# Sheet4.net
KiCad netlist of a schematic drawn in Altium Designer
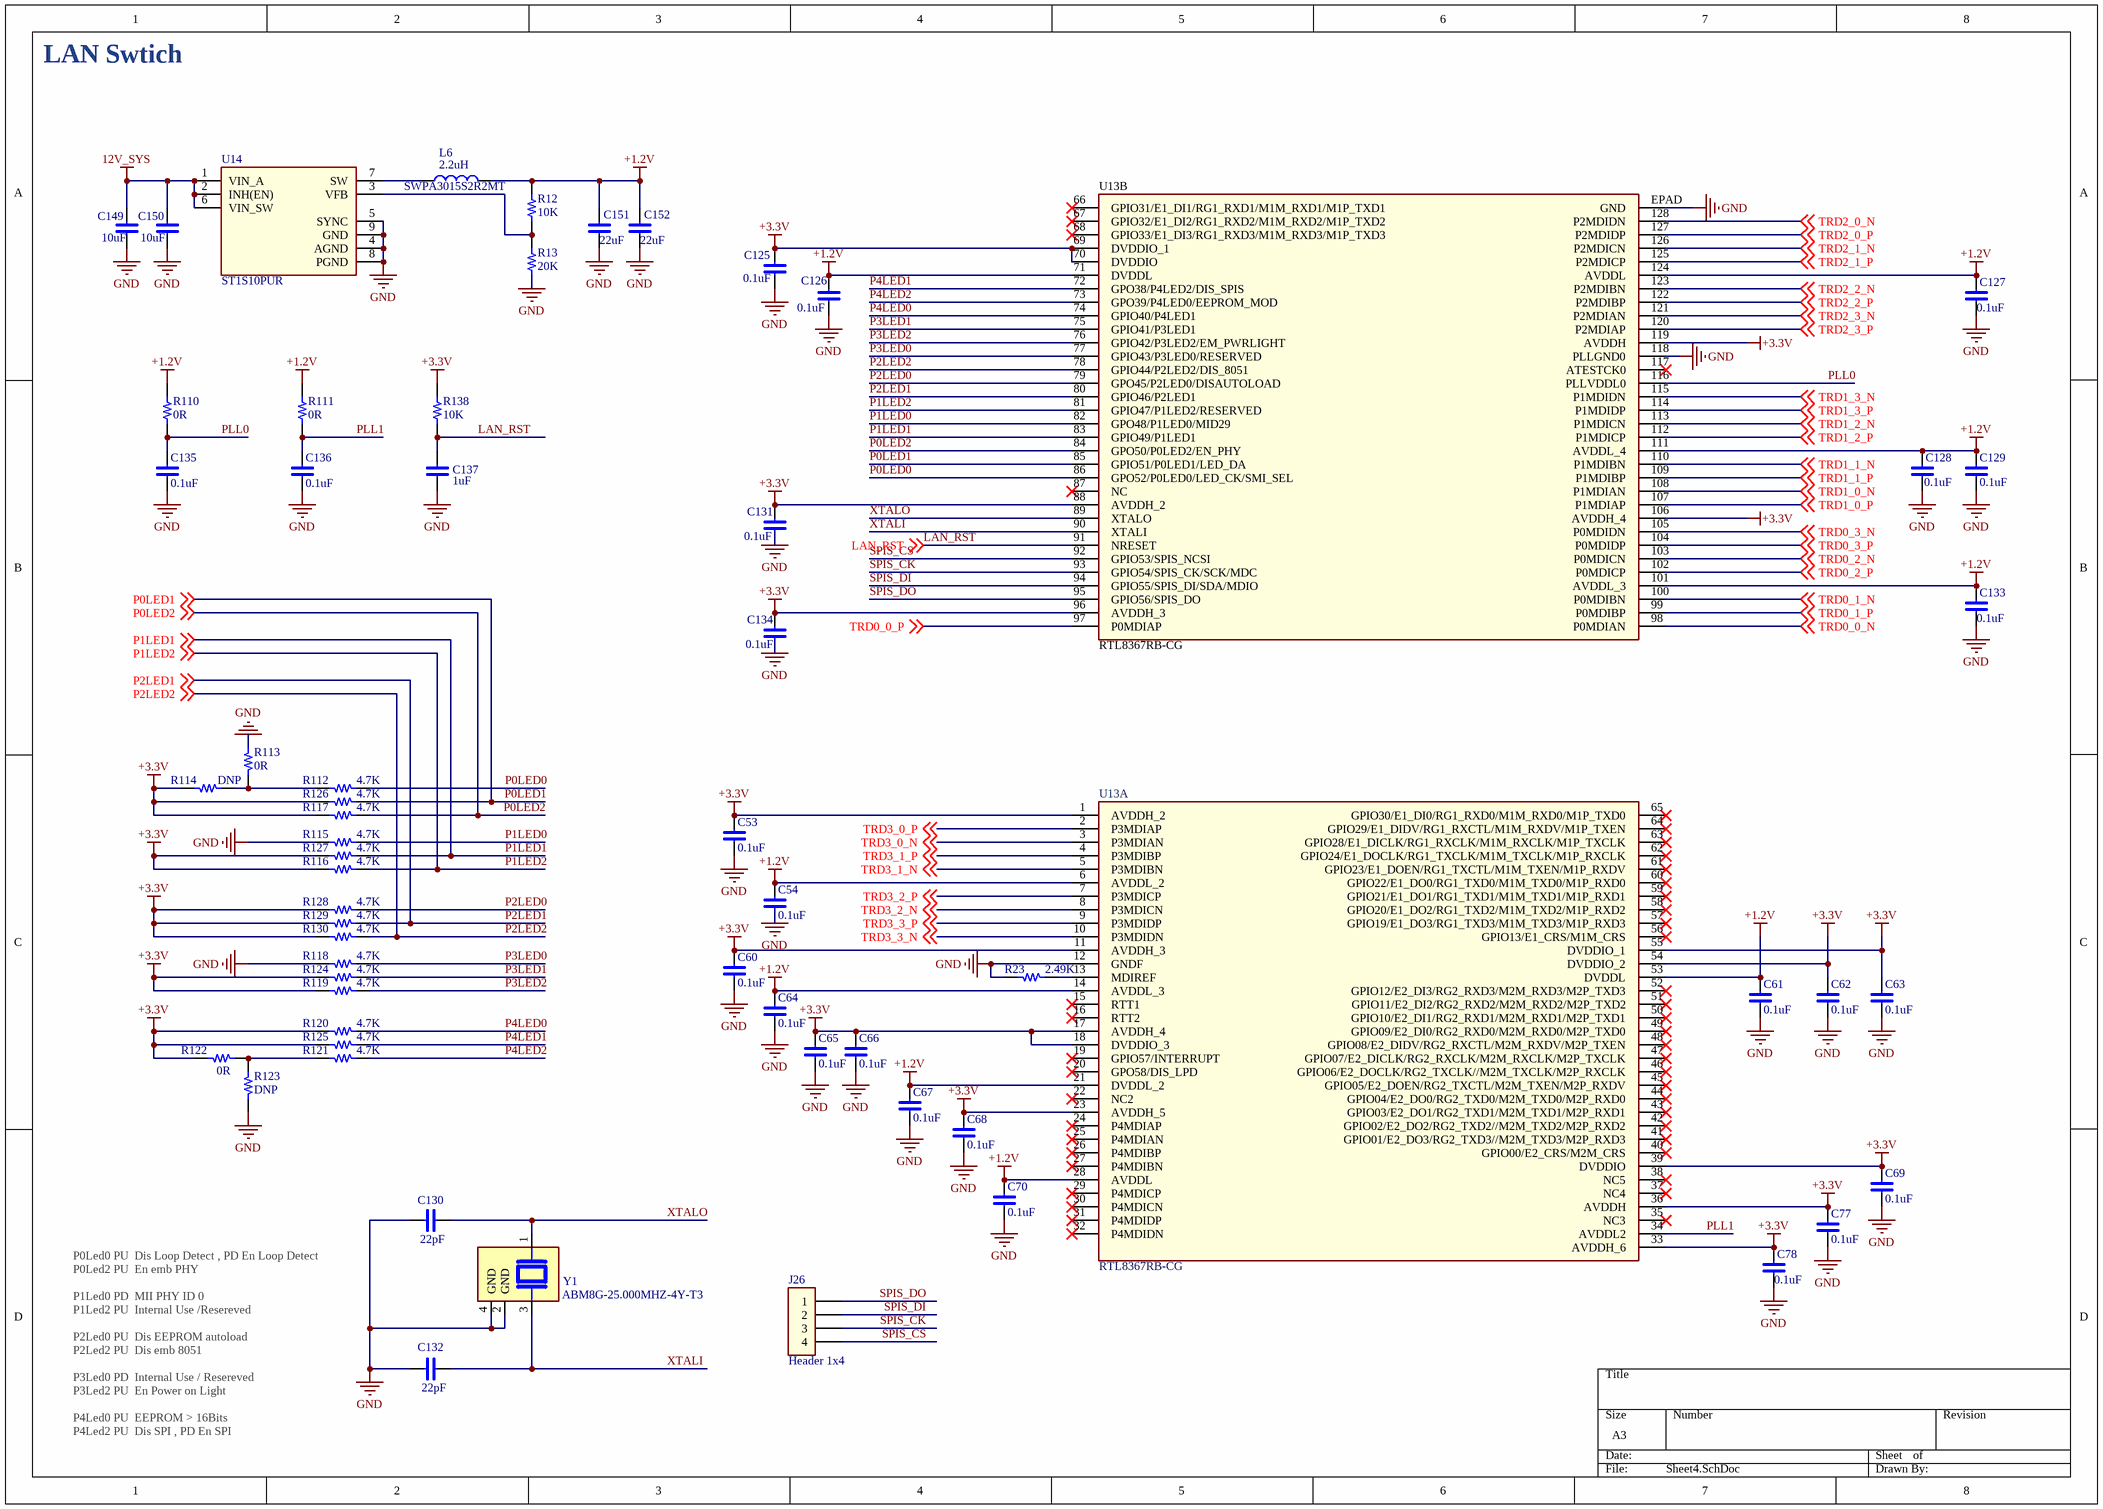
[diagram p0: Sheet4.SchDoc]

(export (version "E")
  (design (tool "Eeschema 10.0.6"))
  (components
    (comp (ref "C53")
      (value "0.1uF")
      (footprint "C-0402/1005")
      (description "CAP CER 0.1UF 16V X7R 0402")
      (fields (field (name "MFR. PART NO.") "GCM155R71C104KA55D"))
      (libsource (lib "Custom_Library") (part "Capacitor-NonPolar"))
    )
    (comp (ref "C54")
      (value "0.1uF")
      (footprint "C-0402/1005")
      (description "CAP CER 0.1UF 16V X7R 0402")
      (fields (field (name "MFR. PART NO.") "GCM155R71C104KA55D"))
      (libsource (lib "Custom_Library") (part "Capacitor-NonPolar"))
    )
    (comp (ref "C60")
      (value "0.1uF")
      (footprint "C-0402/1005")
      (description "CAP CER 0.1UF 16V X7R 0402")
      (fields (field (name "MFR. PART NO.") "GCM155R71C104KA55D"))
      (libsource (lib "Custom_Library") (part "Capacitor-NonPolar"))
    )
    (comp (ref "C61")
      (value "0.1uF")
      (footprint "C-0402/1005")
      (description "CAP CER 0.1UF 16V X7R 0402")
      (fields (field (name "MFR. PART NO.") "GCM155R71C104KA55D"))
      (libsource (lib "Custom_Library") (part "Capacitor-NonPolar"))
    )
    (comp (ref "C62")
      (value "0.1uF")
      (footprint "C-0402/1005")
      (description "CAP CER 0.1UF 16V X7R 0402")
      (fields (field (name "MFR. PART NO.") "GCM155R71C104KA55D"))
      (libsource (lib "Custom_Library") (part "Capacitor-NonPolar"))
    )
    (comp (ref "C63")
      (value "0.1uF")
      (footprint "C-0402/1005")
      (description "CAP CER 0.1UF 16V X7R 0402")
      (fields (field (name "MFR. PART NO.") "GCM155R71C104KA55D"))
      (libsource (lib "Custom_Library") (part "Capacitor-NonPolar"))
    )
    (comp (ref "C64")
      (value "0.1uF")
      (footprint "C-0402/1005")
      (description "CAP CER 0.1UF 16V X7R 0402")
      (fields (field (name "MFR. PART NO.") "GCM155R71C104KA55D"))
      (libsource (lib "Custom_Library") (part "Capacitor-NonPolar"))
    )
    (comp (ref "C65")
      (value "0.1uF")
      (footprint "C-0402/1005")
      (description "CAP CER 0.1UF 16V X7R 0402")
      (fields (field (name "MFR. PART NO.") "GCM155R71C104KA55D"))
      (libsource (lib "Custom_Library") (part "Capacitor-NonPolar"))
    )
    (comp (ref "C66")
      (value "0.1uF")
      (footprint "C-0402/1005")
      (description "CAP CER 0.1UF 16V X7R 0402")
      (fields (field (name "MFR. PART NO.") "GCM155R71C104KA55D"))
      (libsource (lib "Custom_Library") (part "Capacitor-NonPolar"))
    )
    (comp (ref "C67")
      (value "0.1uF")
      (footprint "C-0402/1005")
      (description "CAP CER 0.1UF 16V X7R 0402")
      (fields (field (name "MFR. PART NO.") "GCM155R71C104KA55D"))
      (libsource (lib "Custom_Library") (part "Capacitor-NonPolar"))
    )
    (comp (ref "C68")
      (value "0.1uF")
      (footprint "C-0402/1005")
      (description "CAP CER 0.1UF 16V X7R 0402")
      (fields (field (name "MFR. PART NO.") "GCM155R71C104KA55D"))
      (libsource (lib "Custom_Library") (part "Capacitor-NonPolar"))
    )
    (comp (ref "C69")
      (value "0.1uF")
      (footprint "C-0402/1005")
      (description "CAP CER 0.1UF 16V X7R 0402")
      (fields (field (name "MFR. PART NO.") "GCM155R71C104KA55D"))
      (libsource (lib "Custom_Library") (part "Capacitor-NonPolar"))
    )
    (comp (ref "C70")
      (value "0.1uF")
      (footprint "C-0402/1005")
      (description "CAP CER 0.1UF 16V X7R 0402")
      (fields (field (name "MFR. PART NO.") "GCM155R71C104KA55D"))
      (libsource (lib "Custom_Library") (part "Capacitor-NonPolar"))
    )
    (comp (ref "C77")
      (value "0.1uF")
      (footprint "C-0402/1005")
      (description "CAP CER 0.1UF 16V X7R 0402")
      (fields (field (name "MFR. PART NO.") "GCM155R71C104KA55D"))
      (libsource (lib "Custom_Library") (part "Capacitor-NonPolar"))
    )
    (comp (ref "C78")
      (value "0.1uF")
      (footprint "C-0402/1005")
      (description "CAP CER 0.1UF 16V X7R 0402")
      (fields (field (name "MFR. PART NO.") "GCM155R71C104KA55D"))
      (libsource (lib "Custom_Library") (part "Capacitor-NonPolar"))
    )
    (comp (ref "C125")
      (value "0.1uF")
      (footprint "C-0402/1005")
      (description "CAP CER 0.1UF 16V X7R 0402")
      (fields (field (name "MFR. PART NO.") "GCM155R71C104KA55D"))
      (libsource (lib "Custom_Library") (part "Capacitor-NonPolar"))
    )
    (comp (ref "C126")
      (value "0.1uF")
      (footprint "C-0402/1005")
      (description "CAP CER 0.1UF 16V X7R 0402")
      (fields (field (name "MFR. PART NO.") "GCM155R71C104KA55D"))
      (libsource (lib "Custom_Library") (part "Capacitor-NonPolar"))
    )
    (comp (ref "C127")
      (value "0.1uF")
      (footprint "C-0402/1005")
      (description "CAP CER 0.1UF 16V X7R 0402")
      (fields (field (name "MFR. PART NO.") "GCM155R71C104KA55D"))
      (libsource (lib "Custom_Library") (part "Capacitor-NonPolar"))
    )
    (comp (ref "C128")
      (value "0.1uF")
      (footprint "C-0402/1005")
      (description "CAP CER 0.1UF 16V X7R 0402")
      (fields (field (name "MFR. PART NO.") "GCM155R71C104KA55D"))
      (libsource (lib "Custom_Library") (part "Capacitor-NonPolar"))
    )
    (comp (ref "C129")
      (value "0.1uF")
      (footprint "C-0402/1005")
      (description "CAP CER 0.1UF 16V X7R 0402")
      (fields (field (name "MFR. PART NO.") "GCM155R71C104KA55D"))
      (libsource (lib "Custom_Library") (part "Capacitor-NonPolar"))
    )
    (comp (ref "C130")
      (value "22pF")
      (footprint "C-0402/1005")
      (description "CAP CER 0.1UF 16V X7R 0402")
      (fields (field (name "MFR. PART NO.") "GCM155R71C104KA55D"))
      (libsource (lib "") (part "Capacitor-NonPolar_1"))
    )
    (comp (ref "C131")
      (value "0.1uF")
      (footprint "C-0402/1005")
      (description "CAP CER 0.1UF 16V X7R 0402")
      (fields (field (name "MFR. PART NO.") "GCM155R71C104KA55D"))
      (libsource (lib "Custom_Library") (part "Capacitor-NonPolar"))
    )
    (comp (ref "C132")
      (value "22pF")
      (footprint "C-0402/1005")
      (description "CAP CER 0.1UF 16V X7R 0402")
      (fields (field (name "MFR. PART NO.") "GCM155R71C104KA55D"))
      (libsource (lib "") (part "Capacitor-NonPolar_1"))
    )
    (comp (ref "C133")
      (value "0.1uF")
      (footprint "C-0402/1005")
      (description "CAP CER 0.1UF 16V X7R 0402")
      (fields (field (name "MFR. PART NO.") "GCM155R71C104KA55D"))
      (libsource (lib "Custom_Library") (part "Capacitor-NonPolar"))
    )
    (comp (ref "C134")
      (value "0.1uF")
      (footprint "C-0402/1005")
      (description "CAP CER 0.1UF 16V X7R 0402")
      (fields (field (name "MFR. PART NO.") "GCM155R71C104KA55D"))
      (libsource (lib "Custom_Library") (part "Capacitor-NonPolar"))
    )
    (comp (ref "C135")
      (value "0.1uF")
      (footprint "C-0402/1005")
      (description "CAP CER 0.1UF 16V X7R 0402")
      (fields (field (name "MFR. PART NO.") "GCM155R71C104KA55D"))
      (libsource (lib "Custom_Library") (part "Capacitor-NonPolar"))
    )
    (comp (ref "C136")
      (value "0.1uF")
      (footprint "C-0402/1005")
      (description "CAP CER 0.1UF 16V X7R 0402")
      (fields (field (name "MFR. PART NO.") "GCM155R71C104KA55D"))
      (libsource (lib "Custom_Library") (part "Capacitor-NonPolar"))
    )
    (comp (ref "C137")
      (value "1uF")
      (footprint "C-0402/1005")
      (description "CAP CER 0.1UF 16V X7R 0402")
      (fields (field (name "MFR. PART NO.") "GCM155R71C104KA55D"))
      (libsource (lib "Custom_Library") (part "Capacitor-NonPolar"))
    )
    (comp (ref "C149")
      (value "10uF")
      (footprint "C-0805/2012")
      (description "CAP CER 10UF 25V X5R 1206")
      (fields (field (name "MFR. PART NO.") "C1206C106M3PACTU"))
      (libsource (lib "Custom_Library") (part "CAP 1206/3216"))
    )
    (comp (ref "C150")
      (value "10uF")
      (footprint "C-0805/2012")
      (description "CAP CER 10UF 25V X5R 1206")
      (fields (field (name "MFR. PART NO.") "C1206C106M3PACTU"))
      (libsource (lib "Custom_Library") (part "CAP 1206/3216"))
    )
    (comp (ref "C151")
      (value "22uF")
      (footprint "C-0805/2012")
      (description "CAP CER 10UF 25V X5R 1206")
      (fields (field (name "MFR. PART NO.") "C1206C106M3PACTU"))
      (libsource (lib "Custom_Library") (part "CAP 1206/3216"))
    )
    (comp (ref "C152")
      (value "22uF")
      (footprint "C-0805/2012")
      (description "CAP CER 10UF 25V X5R 1206")
      (fields (field (name "MFR. PART NO.") "C1206C106M3PACTU"))
      (libsource (lib "Custom_Library") (part "CAP 1206/3216"))
    )
    (comp (ref "J26")
      (value "Header 1x4")
      (footprint "PIN HEADER 1x4 2.54mm")
      (description "CONN HEADER VERT 4POS 2.54MM")
      (libsource (lib "Custom_Library") (part "Header 1x4"))
    )
    (comp (ref "L6")
      (value "SWPA3015S2R2MT")
      (footprint "SWPA3015S2R2MT")
      (description "FIXED IND 22UH 620MA 350 MOHM")
      (fields (field (name "MFR. PART NO.") "ASPI-4020S-220M-T") (field (name "ALTIUM_VALUE") "2.2uH"))
      (libsource (lib "Custom_Library") (part "4.3x4.3mm"))
    )
    (comp (ref "R12")
      (value "10K")
      (footprint "R-0402/1005")
      (description "RES SMD 51 OHM 0.5% 1/16W 0402")
      (fields (field (name "MFR. PART NO.") "ERA-2AED510X"))
      (libsource (lib "Custom_Library") (part "Resistor"))
    )
    (comp (ref "R13")
      (value "20K")
      (footprint "R-0402/1005")
      (description "RES SMD 51 OHM 0.5% 1/16W 0402")
      (fields (field (name "MFR. PART NO.") "ERA-2AED510X"))
      (libsource (lib "Custom_Library") (part "Resistor"))
    )
    (comp (ref "R23")
      (value "2.49K")
      (footprint "R-0402/1005")
      (description "RES SMD 51 OHM 0.5% 1/16W 0402")
      (fields (field (name "MFR. PART NO.") "ERA-2AED510X"))
      (libsource (lib "Custom_Library") (part "Resistor"))
    )
    (comp (ref "R110")
      (value "0R")
      (footprint "R-0402/1005")
      (description "RES SMD 1K OHM 1% 1/16W 0402")
      (fields (field (name "MFR. PART NO.") "RC0402FR-071KL"))
      (libsource (lib "Custom_Library") (part "Resistor"))
    )
    (comp (ref "R111")
      (value "0R")
      (footprint "R-0402/1005")
      (description "RES SMD 1K OHM 1% 1/16W 0402")
      (fields (field (name "MFR. PART NO.") "RC0402FR-071KL"))
      (libsource (lib "Custom_Library") (part "Resistor"))
    )
    (comp (ref "R112")
      (value "4.7K")
      (footprint "R-0402/1005")
      (description "RES SMD 1K OHM 1% 1/16W 0402")
      (fields (field (name "MFR. PART NO.") "RC0402FR-071KL"))
      (libsource (lib "Custom_Library") (part "Resistor"))
    )
    (comp (ref "R113")
      (value "0R")
      (footprint "R-0402/1005")
      (description "RES SMD 1K OHM 1% 1/16W 0402")
      (fields (field (name "MFR. PART NO.") "RC0402FR-071KL"))
      (libsource (lib "Custom_Library") (part "Resistor"))
    )
    (comp (ref "R114")
      (value "DNP")
      (footprint "R-0402/1005")
      (description "RES SMD 1K OHM 1% 1/16W 0402")
      (fields (field (name "MFR. PART NO.") "RC0402FR-071KL"))
      (libsource (lib "Custom_Library") (part "Resistor"))
    )
    (comp (ref "R115")
      (value "4.7K")
      (footprint "R-0402/1005")
      (description "RES SMD 1K OHM 1% 1/16W 0402")
      (fields (field (name "MFR. PART NO.") "RC0402FR-071KL"))
      (libsource (lib "Custom_Library") (part "Resistor"))
    )
    (comp (ref "R116")
      (value "4.7K")
      (footprint "R-0402/1005")
      (description "RES SMD 1K OHM 1% 1/16W 0402")
      (fields (field (name "MFR. PART NO.") "RC0402FR-071KL"))
      (libsource (lib "Custom_Library") (part "Resistor"))
    )
    (comp (ref "R117")
      (value "4.7K")
      (footprint "R-0402/1005")
      (description "RES SMD 1K OHM 1% 1/16W 0402")
      (fields (field (name "MFR. PART NO.") "RC0402FR-071KL"))
      (libsource (lib "Custom_Library") (part "Resistor"))
    )
    (comp (ref "R118")
      (value "4.7K")
      (footprint "R-0402/1005")
      (description "RES SMD 1K OHM 1% 1/16W 0402")
      (fields (field (name "MFR. PART NO.") "RC0402FR-071KL"))
      (libsource (lib "Custom_Library") (part "Resistor"))
    )
    (comp (ref "R119")
      (value "4.7K")
      (footprint "R-0402/1005")
      (description "RES SMD 1K OHM 1% 1/16W 0402")
      (fields (field (name "MFR. PART NO.") "RC0402FR-071KL"))
      (libsource (lib "Custom_Library") (part "Resistor"))
    )
    (comp (ref "R120")
      (value "4.7K")
      (footprint "R-0402/1005")
      (description "RES SMD 1K OHM 1% 1/16W 0402")
      (fields (field (name "MFR. PART NO.") "RC0402FR-071KL"))
      (libsource (lib "Custom_Library") (part "Resistor"))
    )
    (comp (ref "R121")
      (value "4.7K")
      (footprint "R-0402/1005")
      (description "RES SMD 1K OHM 1% 1/16W 0402")
      (fields (field (name "MFR. PART NO.") "RC0402FR-071KL"))
      (libsource (lib "Custom_Library") (part "Resistor"))
    )
    (comp (ref "R122")
      (value "0R")
      (footprint "R-0402/1005")
      (description "RES SMD 1K OHM 1% 1/16W 0402")
      (fields (field (name "MFR. PART NO.") "RC0402FR-071KL"))
      (libsource (lib "Custom_Library") (part "Resistor"))
    )
    (comp (ref "R123")
      (value "DNP")
      (footprint "R-0402/1005")
      (description "RES SMD 1K OHM 1% 1/16W 0402")
      (fields (field (name "MFR. PART NO.") "RC0402FR-071KL"))
      (libsource (lib "Custom_Library") (part "Resistor"))
    )
    (comp (ref "R124")
      (value "4.7K")
      (footprint "R-0402/1005")
      (description "RES SMD 1K OHM 1% 1/16W 0402")
      (fields (field (name "MFR. PART NO.") "RC0402FR-071KL"))
      (libsource (lib "Custom_Library") (part "Resistor"))
    )
    (comp (ref "R125")
      (value "4.7K")
      (footprint "R-0402/1005")
      (description "RES SMD 1K OHM 1% 1/16W 0402")
      (fields (field (name "MFR. PART NO.") "RC0402FR-071KL"))
      (libsource (lib "Custom_Library") (part "Resistor"))
    )
    (comp (ref "R126")
      (value "4.7K")
      (footprint "R-0402/1005")
      (description "RES SMD 1K OHM 1% 1/16W 0402")
      (fields (field (name "MFR. PART NO.") "RC0402FR-071KL"))
      (libsource (lib "Custom_Library") (part "Resistor"))
    )
    (comp (ref "R127")
      (value "4.7K")
      (footprint "R-0402/1005")
      (description "RES SMD 1K OHM 1% 1/16W 0402")
      (fields (field (name "MFR. PART NO.") "RC0402FR-071KL"))
      (libsource (lib "Custom_Library") (part "Resistor"))
    )
    (comp (ref "R128")
      (value "4.7K")
      (footprint "R-0402/1005")
      (description "RES SMD 1K OHM 1% 1/16W 0402")
      (fields (field (name "MFR. PART NO.") "RC0402FR-071KL"))
      (libsource (lib "Custom_Library") (part "Resistor"))
    )
    (comp (ref "R129")
      (value "4.7K")
      (footprint "R-0402/1005")
      (description "RES SMD 1K OHM 1% 1/16W 0402")
      (fields (field (name "MFR. PART NO.") "RC0402FR-071KL"))
      (libsource (lib "Custom_Library") (part "Resistor"))
    )
    (comp (ref "R130")
      (value "4.7K")
      (footprint "R-0402/1005")
      (description "RES SMD 1K OHM 1% 1/16W 0402")
      (fields (field (name "MFR. PART NO.") "RC0402FR-071KL"))
      (libsource (lib "Custom_Library") (part "Resistor"))
    )
    (comp (ref "R138")
      (value "10K")
      (footprint "R-0402/1005")
      (description "RES SMD 1K OHM 1% 1/16W 0402")
      (fields (field (name "MFR. PART NO.") "RC0402FR-071KL"))
      (libsource (lib "Custom_Library") (part "Resistor"))
    )
    (comp (ref "U13")
      (value "RTL8367RB-CG")
      (footprint "LQFP128_EPAD_RTK")
      (fields (field (name "COPYRIGHT") "Copyright (C) 2023 Ultra Librarian. All rights reserved."))
      (libsource (lib "RTL8367RB") (part "RTL8367RB-CG"))
    )
    (comp (ref "U14")
      (value "ST1S10PUR")
      (footprint "DFN8_4X4_STM")
      (description "No Description Available")
      (libsource (lib "ST1S10PUR") (part "ST1S10PUR"))
    )
    (comp (ref "Y1")
      (value "ABM8G-25.000MHZ-4Y-T3")
      (footprint "XTAL_ABM8G-25.000MHZ-4Y-T3")
      (description "25 MHz Â±30ppm Crystal 10pF 60 Ohms 4-SMD, No Lead")
      (fields (field (name "MF") "Abracon"))
      (libsource (lib "ABM8G-25.000MHZ-4Y-T3") (part "ABM8G-25.000MHZ-4Y-T3"))
    )
  )
  (nets
    (net (code "1") (name "+1.2V") (class "Default")
      (node (ref "C126") (pin "1") (pinfunction "1_1") (pintype "passive"))
      (node (ref "C127") (pin "1") (pinfunction "1_1") (pintype "passive"))
      (node (ref "C128") (pin "1") (pinfunction "1_1") (pintype "passive"))
      (node (ref "C129") (pin "1") (pinfunction "1_1") (pintype "passive"))
      (node (ref "C133") (pin "1") (pinfunction "1_1") (pintype "passive"))
      (node (ref "C151") (pin "1") (pinfunction "1_1") (pintype "passive"))
      (node (ref "C152") (pin "1") (pinfunction "1_1") (pintype "passive"))
      (node (ref "C54") (pin "1") (pinfunction "1_1") (pintype "passive"))
      (node (ref "C61") (pin "1") (pinfunction "1_1") (pintype "passive"))
      (node (ref "C64") (pin "1") (pinfunction "1_1") (pintype "passive"))
      (node (ref "C67") (pin "1") (pinfunction "1_1") (pintype "passive"))
      (node (ref "C70") (pin "1") (pinfunction "1_1") (pintype "passive"))
      (node (ref "L6") (pin "2") (pinfunction "2_2") (pintype "passive"))
      (node (ref "R110") (pin "2") (pinfunction "2_2") (pintype "passive"))
      (node (ref "R111") (pin "2") (pinfunction "2_2") (pintype "passive"))
      (node (ref "R12") (pin "2") (pinfunction "2_2") (pintype "passive"))
      (node (ref "U13") (pin "101") (pinfunction "AVDDL_3_101") (pintype "passive"))
      (node (ref "U13") (pin "111") (pinfunction "AVDDL_4_111") (pintype "passive"))
      (node (ref "U13") (pin "124") (pinfunction "AVDDL_124") (pintype "passive"))
      (node (ref "U13") (pin "14") (pinfunction "AVDDL_3_14") (pintype "passive"))
      (node (ref "U13") (pin "21") (pinfunction "DVDDL_2_21") (pintype "passive"))
      (node (ref "U13") (pin "28") (pinfunction "AVDDL_28") (pintype "passive"))
      (node (ref "U13") (pin "53") (pinfunction "DVDDL_53") (pintype "passive"))
      (node (ref "U13") (pin "6") (pinfunction "AVDDL_2_6") (pintype "passive"))
      (node (ref "U13") (pin "71") (pinfunction "DVDDL_71") (pintype "passive"))
    )
    (net (code "2") (name "+3.3V") (class "Default")
      (node (ref "C125") (pin "1") (pinfunction "1_1") (pintype "passive"))
      (node (ref "C131") (pin "1") (pinfunction "1_1") (pintype "passive"))
      (node (ref "C134") (pin "1") (pinfunction "1_1") (pintype "passive"))
      (node (ref "C53") (pin "1") (pinfunction "1_1") (pintype "passive"))
      (node (ref "C60") (pin "1") (pinfunction "1_1") (pintype "passive"))
      (node (ref "C62") (pin "1") (pinfunction "1_1") (pintype "passive"))
      (node (ref "C63") (pin "1") (pinfunction "1_1") (pintype "passive"))
      (node (ref "C65") (pin "1") (pinfunction "1_1") (pintype "passive"))
      (node (ref "C66") (pin "1") (pinfunction "1_1") (pintype "passive"))
      (node (ref "C68") (pin "1") (pinfunction "1_1") (pintype "passive"))
      (node (ref "C69") (pin "1") (pinfunction "1_1") (pintype "passive"))
      (node (ref "C77") (pin "1") (pinfunction "1_1") (pintype "passive"))
      (node (ref "C78") (pin "1") (pinfunction "1_1") (pintype "passive"))
      (node (ref "R114") (pin "2") (pinfunction "2_2") (pintype "passive"))
      (node (ref "R116") (pin "2") (pinfunction "2_2") (pintype "passive"))
      (node (ref "R117") (pin "2") (pinfunction "2_2") (pintype "passive"))
      (node (ref "R119") (pin "2") (pinfunction "2_2") (pintype "passive"))
      (node (ref "R120") (pin "2") (pinfunction "2_2") (pintype "passive"))
      (node (ref "R122") (pin "2") (pinfunction "2_2") (pintype "passive"))
      (node (ref "R124") (pin "2") (pinfunction "2_2") (pintype "passive"))
      (node (ref "R125") (pin "2") (pinfunction "2_2") (pintype "passive"))
      (node (ref "R126") (pin "2") (pinfunction "2_2") (pintype "passive"))
      (node (ref "R127") (pin "2") (pinfunction "2_2") (pintype "passive"))
      (node (ref "R128") (pin "2") (pinfunction "2_2") (pintype "passive"))
      (node (ref "R129") (pin "2") (pinfunction "2_2") (pintype "passive"))
      (node (ref "R130") (pin "2") (pinfunction "2_2") (pintype "passive"))
      (node (ref "R138") (pin "2") (pinfunction "2_2") (pintype "passive"))
      (node (ref "U13") (pin "1") (pinfunction "AVDDH_2_1") (pintype "passive"))
      (node (ref "U13") (pin "106") (pinfunction "AVDDH_4_106") (pintype "passive"))
      (node (ref "U13") (pin "11") (pinfunction "AVDDH_3_11") (pintype "passive"))
      (node (ref "U13") (pin "119") (pinfunction "AVDDH_119") (pintype "passive"))
      (node (ref "U13") (pin "17") (pinfunction "AVDDH_4_17") (pintype "passive"))
      (node (ref "U13") (pin "18") (pinfunction "DVDDIO_3_18") (pintype "passive"))
      (node (ref "U13") (pin "23") (pinfunction "AVDDH_5_23") (pintype "passive"))
      (node (ref "U13") (pin "33") (pinfunction "AVDDH_6_33") (pintype "passive"))
      (node (ref "U13") (pin "36") (pinfunction "AVDDH_36") (pintype "passive"))
      (node (ref "U13") (pin "39") (pinfunction "DVDDIO_39") (pintype "passive"))
      (node (ref "U13") (pin "54") (pinfunction "DVDDIO_2_54") (pintype "passive"))
      (node (ref "U13") (pin "55") (pinfunction "DVDDIO_1_55") (pintype "passive"))
      (node (ref "U13") (pin "69") (pinfunction "DVDDIO_1_69") (pintype "passive"))
      (node (ref "U13") (pin "70") (pinfunction "DVDDIO_70") (pintype "passive"))
      (node (ref "U13") (pin "88") (pinfunction "AVDDH_2_88") (pintype "passive"))
      (node (ref "U13") (pin "96") (pinfunction "AVDDH_3_96") (pintype "passive"))
    )
    (net (code "3") (name "/P0LED0") (class "Default")
      (node (ref "R112") (pin "1") (pinfunction "1_1") (pintype "passive"))
      (node (ref "U13") (pin "86") (pinfunction "GPO52/P0LED0/LED_CK/SMI_SEL_86") (pintype "passive"))
    )
    (net (code "4") (name "/P1LED0") (class "Default")
      (node (ref "R115") (pin "1") (pinfunction "1_1") (pintype "passive"))
      (node (ref "U13") (pin "82") (pinfunction "GPO48/P1LED0/MID29_82") (pintype "passive"))
    )
    (net (code "5") (name "/P2LED0") (class "Default")
      (node (ref "R128") (pin "1") (pinfunction "1_1") (pintype "passive"))
      (node (ref "U13") (pin "79") (pinfunction "GPO45/P2LED0/DISAUTOLOAD_79") (pintype "passive"))
    )
    (net (code "6") (name "/P3LED0") (class "Default")
      (node (ref "R118") (pin "1") (pinfunction "1_1") (pintype "passive"))
      (node (ref "U13") (pin "77") (pinfunction "GPIO43/P3LED0/RESERVED_77") (pintype "passive"))
    )
    (net (code "7") (name "/P3LED1") (class "Default")
      (node (ref "R124") (pin "1") (pinfunction "1_1") (pintype "passive"))
      (node (ref "U13") (pin "75") (pinfunction "GPIO41/P3LED1_75") (pintype "passive"))
    )
    (net (code "8") (name "/P3LED2") (class "Default")
      (node (ref "R119") (pin "1") (pinfunction "1_1") (pintype "passive"))
      (node (ref "U13") (pin "76") (pinfunction "GPIO42/P3LED2/EM_PWRLIGHT_76") (pintype "passive"))
    )
    (net (code "9") (name "/P4LED0") (class "Default")
      (node (ref "R120") (pin "1") (pinfunction "1_1") (pintype "passive"))
      (node (ref "U13") (pin "74") (pinfunction "GPIO40/P4LED1_74") (pintype "passive"))
    )
    (net (code "10") (name "/P4LED1") (class "Default")
      (node (ref "R125") (pin "1") (pinfunction "1_1") (pintype "passive"))
      (node (ref "U13") (pin "72") (pinfunction "GPO38/P4LED2/DIS_SPIS_72") (pintype "passive"))
    )
    (net (code "11") (name "/P4LED2") (class "Default")
      (node (ref "R121") (pin "1") (pinfunction "1_1") (pintype "passive"))
      (node (ref "U13") (pin "73") (pinfunction "GPO39/P4LED0/EEPROM_MOD_73") (pintype "passive"))
    )
    (net (code "12") (name "/PLL0") (class "Default")
      (node (ref "C135") (pin "1") (pinfunction "1_1") (pintype "passive"))
      (node (ref "R110") (pin "1") (pinfunction "1_1") (pintype "passive"))
      (node (ref "U13") (pin "116") (pinfunction "PLLVDDL0_116") (pintype "passive"))
    )
    (net (code "13") (name "/PLL1") (class "Default")
      (node (ref "C136") (pin "1") (pinfunction "1_1") (pintype "passive"))
      (node (ref "R111") (pin "1") (pinfunction "1_1") (pintype "passive"))
      (node (ref "U13") (pin "34") (pinfunction "AVDDL2_34") (pintype "passive"))
    )
    (net (code "14") (name "/SPIS_CK") (class "Default")
      (node (ref "J26") (pin "3") (pinfunction "3_3") (pintype "passive"))
      (node (ref "U13") (pin "93") (pinfunction "GPIO54/SPIS_CK/SCK/MDC_93") (pintype "passive"))
    )
    (net (code "15") (name "/SPIS_CS") (class "Default")
      (node (ref "J26") (pin "4") (pinfunction "4_4") (pintype "passive"))
      (node (ref "U13") (pin "92") (pinfunction "GPIO53/SPIS_NCSI_92") (pintype "passive"))
    )
    (net (code "16") (name "/SPIS_DI") (class "Default")
      (node (ref "J26") (pin "2") (pinfunction "2_2") (pintype "passive"))
      (node (ref "U13") (pin "94") (pinfunction "GPIO55/SPIS_DI/SDA/MDIO_94") (pintype "passive"))
    )
    (net (code "17") (name "/SPIS_DO") (class "Default")
      (node (ref "J26") (pin "1") (pinfunction "1_1") (pintype "passive"))
      (node (ref "U13") (pin "95") (pinfunction "GPIO56/SPIS_DO_95") (pintype "passive"))
    )
    (net (code "18") (name "/XTALI") (class "Default")
      (node (ref "C132") (pin "2") (pinfunction "2_2") (pintype "passive"))
      (node (ref "U13") (pin "90") (pinfunction "XTALI_90") (pintype "passive"))
      (node (ref "Y1") (pin "3") (pinfunction "2_3") (pintype "passive"))
    )
    (net (code "19") (name "/XTALO") (class "Default")
      (node (ref "C130") (pin "2") (pinfunction "2_2") (pintype "passive"))
      (node (ref "U13") (pin "89") (pinfunction "XTALO_89") (pintype "passive"))
      (node (ref "Y1") (pin "1") (pinfunction "1_1") (pintype "passive"))
    )
    (net (code "20") (name "12V_SYS") (class "Default")
      (node (ref "C149") (pin "1") (pinfunction "1_1") (pintype "passive"))
      (node (ref "C150") (pin "1") (pinfunction "1_1") (pintype "passive"))
      (node (ref "U14") (pin "1") (pinfunction "VIN_A_1") (pintype "passive"))
      (node (ref "U14") (pin "2") (pinfunction "INH(EN)_2") (pintype "passive"))
      (node (ref "U14") (pin "6") (pinfunction "VIN_SW_6") (pintype "passive"))
    )
    (net (code "21") (name "GND") (class "Default")
      (node (ref "C125") (pin "2") (pinfunction "2_2") (pintype "passive"))
      (node (ref "C126") (pin "2") (pinfunction "2_2") (pintype "passive"))
      (node (ref "C127") (pin "2") (pinfunction "2_2") (pintype "passive"))
      (node (ref "C128") (pin "2") (pinfunction "2_2") (pintype "passive"))
      (node (ref "C129") (pin "2") (pinfunction "2_2") (pintype "passive"))
      (node (ref "C130") (pin "1") (pinfunction "1_1") (pintype "passive"))
      (node (ref "C131") (pin "2") (pinfunction "2_2") (pintype "passive"))
      (node (ref "C132") (pin "1") (pinfunction "1_1") (pintype "passive"))
      (node (ref "C133") (pin "2") (pinfunction "2_2") (pintype "passive"))
      (node (ref "C134") (pin "2") (pinfunction "2_2") (pintype "passive"))
      (node (ref "C135") (pin "2") (pinfunction "2_2") (pintype "passive"))
      (node (ref "C136") (pin "2") (pinfunction "2_2") (pintype "passive"))
      (node (ref "C137") (pin "2") (pinfunction "2_2") (pintype "passive"))
      (node (ref "C149") (pin "2") (pinfunction "2_2") (pintype "passive"))
      (node (ref "C150") (pin "2") (pinfunction "2_2") (pintype "passive"))
      (node (ref "C151") (pin "2") (pinfunction "2_2") (pintype "passive"))
      (node (ref "C152") (pin "2") (pinfunction "2_2") (pintype "passive"))
      (node (ref "C53") (pin "2") (pinfunction "2_2") (pintype "passive"))
      (node (ref "C54") (pin "2") (pinfunction "2_2") (pintype "passive"))
      (node (ref "C60") (pin "2") (pinfunction "2_2") (pintype "passive"))
      (node (ref "C61") (pin "2") (pinfunction "2_2") (pintype "passive"))
      (node (ref "C62") (pin "2") (pinfunction "2_2") (pintype "passive"))
      (node (ref "C63") (pin "2") (pinfunction "2_2") (pintype "passive"))
      (node (ref "C64") (pin "2") (pinfunction "2_2") (pintype "passive"))
      (node (ref "C65") (pin "2") (pinfunction "2_2") (pintype "passive"))
      (node (ref "C66") (pin "2") (pinfunction "2_2") (pintype "passive"))
      (node (ref "C67") (pin "2") (pinfunction "2_2") (pintype "passive"))
      (node (ref "C68") (pin "2") (pinfunction "2_2") (pintype "passive"))
      (node (ref "C69") (pin "2") (pinfunction "2_2") (pintype "passive"))
      (node (ref "C70") (pin "2") (pinfunction "2_2") (pintype "passive"))
      (node (ref "C77") (pin "2") (pinfunction "2_2") (pintype "passive"))
      (node (ref "C78") (pin "2") (pinfunction "2_2") (pintype "passive"))
      (node (ref "R113") (pin "2") (pinfunction "2_2") (pintype "passive"))
      (node (ref "R115") (pin "2") (pinfunction "2_2") (pintype "passive"))
      (node (ref "R118") (pin "2") (pinfunction "2_2") (pintype "passive"))
      (node (ref "R123") (pin "2") (pinfunction "2_2") (pintype "passive"))
      (node (ref "R13") (pin "2") (pinfunction "2_2") (pintype "passive"))
      (node (ref "R23") (pin "2") (pinfunction "2_2") (pintype "passive"))
      (node (ref "U13") (pin "118") (pinfunction "PLLGND0_118") (pintype "passive"))
      (node (ref "U13") (pin "12") (pinfunction "GNDF_12") (pintype "passive"))
      (node (ref "U13") (pin "EPAD") (pinfunction "GND_EPAD") (pintype "passive"))
      (node (ref "U14") (pin "4") (pinfunction "AGND_4") (pintype "passive"))
      (node (ref "U14") (pin "5") (pinfunction "SYNC_5") (pintype "passive"))
      (node (ref "U14") (pin "8") (pinfunction "PGND_8") (pintype "passive"))
      (node (ref "U14") (pin "9") (pinfunction "GND_9") (pintype "passive"))
      (node (ref "Y1") (pin "2") (pinfunction "GND_2") (pintype "power_in"))
      (node (ref "Y1") (pin "4") (pinfunction "GND_4") (pintype "power_in"))
    )
    (net (code "22") (name "LAN_RST") (class "Default")
      (node (ref "C137") (pin "1") (pinfunction "1_1") (pintype "passive"))
      (node (ref "R138") (pin "1") (pinfunction "1_1") (pintype "passive"))
      (node (ref "U13") (pin "91") (pinfunction "NRESET_91") (pintype "passive"))
    )
    (net (code "23") (name "Net-(R112-Pad2)") (class "Default")
      (node (ref "R112") (pin "2") (pinfunction "2_2") (pintype "passive"))
      (node (ref "R113") (pin "1") (pinfunction "1_1") (pintype "passive"))
      (node (ref "R114") (pin "1") (pinfunction "1_1") (pintype "passive"))
    )
    (net (code "24") (name "Net-(R121-Pad2)") (class "Default")
      (node (ref "R121") (pin "2") (pinfunction "2_2") (pintype "passive"))
      (node (ref "R122") (pin "1") (pinfunction "1_1") (pintype "passive"))
      (node (ref "R123") (pin "1") (pinfunction "1_1") (pintype "passive"))
    )
    (net (code "25") (name "Net-(U13A-MDIREF)") (class "Default")
      (node (ref "R23") (pin "1") (pinfunction "1_1") (pintype "passive"))
      (node (ref "U13") (pin "13") (pinfunction "MDIREF_13") (pintype "passive"))
    )
    (net (code "26") (name "Net-(U14-SW)") (class "Default")
      (node (ref "L6") (pin "1") (pinfunction "1_1") (pintype "passive"))
      (node (ref "U14") (pin "7") (pinfunction "SW_7") (pintype "passive"))
    )
    (net (code "27") (name "Net-(U14-VFB)") (class "Default")
      (node (ref "R12") (pin "1") (pinfunction "1_1") (pintype "passive"))
      (node (ref "R13") (pin "1") (pinfunction "1_1") (pintype "passive"))
      (node (ref "U14") (pin "3") (pinfunction "VFB_3") (pintype "passive"))
    )
    (net (code "28") (name "P0LED1") (class "Default")
      (node (ref "R126") (pin "1") (pinfunction "1_1") (pintype "passive"))
      (node (ref "U13") (pin "85") (pinfunction "GPIO51/P0LED1/LED_DA_85") (pintype "passive"))
    )
    (net (code "29") (name "P0LED2") (class "Default")
      (node (ref "R117") (pin "1") (pinfunction "1_1") (pintype "passive"))
      (node (ref "U13") (pin "84") (pinfunction "GPO50/P0LED2/EN_PHY_84") (pintype "passive"))
    )
    (net (code "30") (name "P1LED1") (class "Default")
      (node (ref "R127") (pin "1") (pinfunction "1_1") (pintype "passive"))
      (node (ref "U13") (pin "83") (pinfunction "GPIO49/P1LED1_83") (pintype "passive"))
    )
    (net (code "31") (name "P1LED2") (class "Default")
      (node (ref "R116") (pin "1") (pinfunction "1_1") (pintype "passive"))
      (node (ref "U13") (pin "81") (pinfunction "GPIO47/P1LED2/RESERVED_81") (pintype "passive"))
    )
    (net (code "32") (name "P2LED1") (class "Default")
      (node (ref "R129") (pin "1") (pinfunction "1_1") (pintype "passive"))
      (node (ref "U13") (pin "80") (pinfunction "GPIO46/P2LED1_80") (pintype "passive"))
    )
    (net (code "33") (name "P2LED2") (class "Default")
      (node (ref "R130") (pin "1") (pinfunction "1_1") (pintype "passive"))
      (node (ref "U13") (pin "78") (pinfunction "GPIO44/P2LED2/DIS_8051_78") (pintype "passive"))
    )
    (net (code "34") (name "TRD0_0_N") (class "Default")
      (node (ref "U13") (pin "98") (pinfunction "P0MDIAN_98") (pintype "passive"))
    )
    (net (code "35") (name "TRD0_0_P") (class "Default")
      (node (ref "U13") (pin "97") (pinfunction "P0MDIAP_97") (pintype "passive"))
    )
    (net (code "36") (name "TRD0_1_N") (class "Default")
      (node (ref "U13") (pin "100") (pinfunction "P0MDIBN_100") (pintype "passive"))
    )
    (net (code "37") (name "TRD0_1_P") (class "Default")
      (node (ref "U13") (pin "99") (pinfunction "P0MDIBP_99") (pintype "passive"))
    )
    (net (code "38") (name "TRD0_2_N") (class "Default")
      (node (ref "U13") (pin "103") (pinfunction "P0MDICN_103") (pintype "passive"))
    )
    (net (code "39") (name "TRD0_2_P") (class "Default")
      (node (ref "U13") (pin "102") (pinfunction "P0MDICP_102") (pintype "passive"))
    )
    (net (code "40") (name "TRD0_3_N") (class "Default")
      (node (ref "U13") (pin "105") (pinfunction "P0MDIDN_105") (pintype "passive"))
    )
    (net (code "41") (name "TRD0_3_P") (class "Default")
      (node (ref "U13") (pin "104") (pinfunction "P0MDIDP_104") (pintype "passive"))
    )
    (net (code "42") (name "TRD1_0_N") (class "Default")
      (node (ref "U13") (pin "108") (pinfunction "P1MDIAN_108") (pintype "passive"))
    )
    (net (code "43") (name "TRD1_0_P") (class "Default")
      (node (ref "U13") (pin "107") (pinfunction "P1MDIAP_107") (pintype "passive"))
    )
    (net (code "44") (name "TRD1_1_N") (class "Default")
      (node (ref "U13") (pin "110") (pinfunction "P1MDIBN_110") (pintype "passive"))
    )
    (net (code "45") (name "TRD1_1_P") (class "Default")
      (node (ref "U13") (pin "109") (pinfunction "P1MDIBP_109") (pintype "passive"))
    )
    (net (code "46") (name "TRD1_2_N") (class "Default")
      (node (ref "U13") (pin "113") (pinfunction "P1MDICN_113") (pintype "passive"))
    )
    (net (code "47") (name "TRD1_2_P") (class "Default")
      (node (ref "U13") (pin "112") (pinfunction "P1MDICP_112") (pintype "passive"))
    )
    (net (code "48") (name "TRD1_3_N") (class "Default")
      (node (ref "U13") (pin "115") (pinfunction "P1MDIDN_115") (pintype "passive"))
    )
    (net (code "49") (name "TRD1_3_P") (class "Default")
      (node (ref "U13") (pin "114") (pinfunction "P1MDIDP_114") (pintype "passive"))
    )
    (net (code "50") (name "TRD2_0_N") (class "Default")
      (node (ref "U13") (pin "128") (pinfunction "P2MDIDN_128") (pintype "passive"))
    )
    (net (code "51") (name "TRD2_0_P") (class "Default")
      (node (ref "U13") (pin "127") (pinfunction "P2MDIDP_127") (pintype "passive"))
    )
    (net (code "52") (name "TRD2_1_N") (class "Default")
      (node (ref "U13") (pin "126") (pinfunction "P2MDICN_126") (pintype "passive"))
    )
    (net (code "53") (name "TRD2_1_P") (class "Default")
      (node (ref "U13") (pin "125") (pinfunction "P2MDICP_125") (pintype "passive"))
    )
    (net (code "54") (name "TRD2_2_N") (class "Default")
      (node (ref "U13") (pin "123") (pinfunction "P2MDIBN_123") (pintype "passive"))
    )
    (net (code "55") (name "TRD2_2_P") (class "Default")
      (node (ref "U13") (pin "122") (pinfunction "P2MDIBP_122") (pintype "passive"))
    )
    (net (code "56") (name "TRD2_3_N") (class "Default")
      (node (ref "U13") (pin "121") (pinfunction "P2MDIAN_121") (pintype "passive"))
    )
    (net (code "57") (name "TRD2_3_P") (class "Default")
      (node (ref "U13") (pin "120") (pinfunction "P2MDIAP_120") (pintype "passive"))
    )
    (net (code "58") (name "TRD3_0_N") (class "Default")
      (node (ref "U13") (pin "3") (pinfunction "P3MDIAN_3") (pintype "passive"))
    )
    (net (code "59") (name "TRD3_0_P") (class "Default")
      (node (ref "U13") (pin "2") (pinfunction "P3MDIAP_2") (pintype "passive"))
    )
    (net (code "60") (name "TRD3_1_N") (class "Default")
      (node (ref "U13") (pin "5") (pinfunction "P3MDIBN_5") (pintype "passive"))
    )
    (net (code "61") (name "TRD3_1_P") (class "Default")
      (node (ref "U13") (pin "4") (pinfunction "P3MDIBP_4") (pintype "passive"))
    )
    (net (code "62") (name "TRD3_2_N") (class "Default")
      (node (ref "U13") (pin "8") (pinfunction "P3MDICN_8") (pintype "passive"))
    )
    (net (code "63") (name "TRD3_2_P") (class "Default")
      (node (ref "U13") (pin "7") (pinfunction "P3MDICP_7") (pintype "passive"))
    )
    (net (code "64") (name "TRD3_3_N") (class "Default")
      (node (ref "U13") (pin "10") (pinfunction "P3MDIDN_10") (pintype "passive"))
    )
    (net (code "65") (name "TRD3_3_P") (class "Default")
      (node (ref "U13") (pin "9") (pinfunction "P3MDIDP_9") (pintype "passive"))
    )
    (net (code "66") (name "unconnected-(U13A-GPIO00{slash}E2_CRS{slash}M2M_CRS-Pad40)") (class "Default")
      (node (ref "U13") (pin "40") (pinfunction "GPIO00/E2_CRS/M2M_CRS_40") (pintype "passive+no_connect"))
    )
    (net (code "67") (name "unconnected-(U13A-GPIO01{slash}E2_DO3{slash}RG2_TXD3{slash}{slash}M2M_TXD3{slash}M2P_RXD3-Pad41)") (class "Default")
      (node (ref "U13") (pin "41") (pinfunction "GPIO01/E2_DO3/RG2_TXD3//M2M_TXD3/M2P_RXD3_41") (pintype "passive+no_connect"))
    )
    (net (code "68") (name "unconnected-(U13A-GPIO02{slash}E2_DO2{slash}RG2_TXD2{slash}{slash}M2M_TXD2{slash}M2P_RXD2-Pad42)") (class "Default")
      (node (ref "U13") (pin "42") (pinfunction "GPIO02/E2_DO2/RG2_TXD2//M2M_TXD2/M2P_RXD2_42") (pintype "passive+no_connect"))
    )
    (net (code "69") (name "unconnected-(U13A-GPIO03{slash}E2_DO1{slash}RG2_TXD1{slash}M2M_TXD1{slash}M2P_RXD1-Pad43)") (class "Default")
      (node (ref "U13") (pin "43") (pinfunction "GPIO03/E2_DO1/RG2_TXD1/M2M_TXD1/M2P_RXD1_43") (pintype "passive+no_connect"))
    )
    (net (code "70") (name "unconnected-(U13A-GPIO04{slash}E2_DO0{slash}RG2_TXD0{slash}M2M_TXD0{slash}M2P_RXD0-Pad44)") (class "Default")
      (node (ref "U13") (pin "44") (pinfunction "GPIO04/E2_DO0/RG2_TXD0/M2M_TXD0/M2P_RXD0_44") (pintype "passive+no_connect"))
    )
    (net (code "71") (name "unconnected-(U13A-GPIO05{slash}E2_DOEN{slash}RG2_TXCTL{slash}M2M_TXEN{slash}M2P_RXDV-Pad45)") (class "Default")
      (node (ref "U13") (pin "45") (pinfunction "GPIO05/E2_DOEN/RG2_TXCTL/M2M_TXEN/M2P_RXDV_45") (pintype "passive+no_connect"))
    )
    (net (code "72") (name "unconnected-(U13A-GPIO06{slash}E2_DOCLK{slash}RG2_TXCLK{slash}{slash}M2M_TXCLK{slash}M2P_RXCLK-Pad46)") (class "Default")
      (node (ref "U13") (pin "46") (pinfunction "GPIO06/E2_DOCLK/RG2_TXCLK//M2M_TXCLK/M2P_RXCLK_46") (pintype "passive+no_connect"))
    )
    (net (code "73") (name "unconnected-(U13A-GPIO07{slash}E2_DICLK{slash}RG2_RXCLK{slash}M2M_RXCLK{slash}M2P_TXCLK-Pad47)") (class "Default")
      (node (ref "U13") (pin "47") (pinfunction "GPIO07/E2_DICLK/RG2_RXCLK/M2M_RXCLK/M2P_TXCLK_47") (pintype "passive+no_connect"))
    )
    (net (code "74") (name "unconnected-(U13A-GPIO08{slash}E2_DIDV{slash}RG2_RXCTL{slash}M2M_RXDV{slash}M2P_TXEN-Pad48)") (class "Default")
      (node (ref "U13") (pin "48") (pinfunction "GPIO08/E2_DIDV/RG2_RXCTL/M2M_RXDV/M2P_TXEN_48") (pintype "passive+no_connect"))
    )
    (net (code "75") (name "unconnected-(U13A-GPIO09{slash}E2_DI0{slash}RG2_RXD0{slash}M2M_RXD0{slash}M2P_TXD0-Pad49)") (class "Default")
      (node (ref "U13") (pin "49") (pinfunction "GPIO09/E2_DI0/RG2_RXD0/M2M_RXD0/M2P_TXD0_49") (pintype "passive+no_connect"))
    )
    (net (code "76") (name "unconnected-(U13A-GPIO10{slash}E2_DI1{slash}RG2_RXD1{slash}M2M_RXD1{slash}M2P_TXD1-Pad50)") (class "Default")
      (node (ref "U13") (pin "50") (pinfunction "GPIO10/E2_DI1/RG2_RXD1/M2M_RXD1/M2P_TXD1_50") (pintype "passive+no_connect"))
    )
    (net (code "77") (name "unconnected-(U13A-GPIO11{slash}E2_DI2{slash}RG2_RXD2{slash}M2M_RXD2{slash}M2P_TXD2-Pad51)") (class "Default")
      (node (ref "U13") (pin "51") (pinfunction "GPIO11/E2_DI2/RG2_RXD2/M2M_RXD2/M2P_TXD2_51") (pintype "passive+no_connect"))
    )
    (net (code "78") (name "unconnected-(U13A-GPIO12{slash}E2_DI3{slash}RG2_RXD3{slash}M2M_RXD3{slash}M2P_TXD3-Pad52)") (class "Default")
      (node (ref "U13") (pin "52") (pinfunction "GPIO12/E2_DI3/RG2_RXD3/M2M_RXD3/M2P_TXD3_52") (pintype "passive+no_connect"))
    )
    (net (code "79") (name "unconnected-(U13A-GPIO13{slash}E1_CRS{slash}M1M_CRS-Pad56)") (class "Default")
      (node (ref "U13") (pin "56") (pinfunction "GPIO13/E1_CRS/M1M_CRS_56") (pintype "passive+no_connect"))
    )
    (net (code "80") (name "unconnected-(U13A-GPIO19{slash}E1_DO3{slash}RG1_TXD3{slash}M1M_TXD3{slash}M1P_RXD3-Pad57)") (class "Default")
      (node (ref "U13") (pin "57") (pinfunction "GPIO19/E1_DO3/RG1_TXD3/M1M_TXD3/M1P_RXD3_57") (pintype "passive+no_connect"))
    )
    (net (code "81") (name "unconnected-(U13A-GPIO20{slash}E1_DO2{slash}RG1_TXD2{slash}M1M_TXD2{slash}M1P_RXD2-Pad58)") (class "Default")
      (node (ref "U13") (pin "58") (pinfunction "GPIO20/E1_DO2/RG1_TXD2/M1M_TXD2/M1P_RXD2_58") (pintype "passive+no_connect"))
    )
    (net (code "82") (name "unconnected-(U13A-GPIO21{slash}E1_DO1{slash}RG1_TXD1{slash}M1M_TXD1{slash}M1P_RXD1-Pad59)") (class "Default")
      (node (ref "U13") (pin "59") (pinfunction "GPIO21/E1_DO1/RG1_TXD1/M1M_TXD1/M1P_RXD1_59") (pintype "passive+no_connect"))
    )
    (net (code "83") (name "unconnected-(U13A-GPIO22{slash}E1_DO0{slash}RG1_TXD0{slash}M1M_TXD0{slash}M1P_RXD0-Pad60)") (class "Default")
      (node (ref "U13") (pin "60") (pinfunction "GPIO22/E1_DO0/RG1_TXD0/M1M_TXD0/M1P_RXD0_60") (pintype "passive+no_connect"))
    )
    (net (code "84") (name "unconnected-(U13A-GPIO23{slash}E1_DOEN{slash}RG1_TXCTL{slash}M1M_TXEN{slash}M1P_RXDV-Pad61)") (class "Default")
      (node (ref "U13") (pin "61") (pinfunction "GPIO23/E1_DOEN/RG1_TXCTL/M1M_TXEN/M1P_RXDV_61") (pintype "passive+no_connect"))
    )
    (net (code "85") (name "unconnected-(U13A-GPIO24{slash}E1_DOCLK{slash}RG1_TXCLK{slash}M1M_TXCLK{slash}M1P_RXCLK-Pad62)") (class "Default")
      (node (ref "U13") (pin "62") (pinfunction "GPIO24/E1_DOCLK/RG1_TXCLK/M1M_TXCLK/M1P_RXCLK_62") (pintype "passive+no_connect"))
    )
    (net (code "86") (name "unconnected-(U13A-GPIO28{slash}E1_DICLK{slash}RG1_RXCLK{slash}M1M_RXCLK{slash}M1P_TXCLK-Pad63)") (class "Default")
      (node (ref "U13") (pin "63") (pinfunction "GPIO28/E1_DICLK/RG1_RXCLK/M1M_RXCLK/M1P_TXCLK_63") (pintype "passive+no_connect"))
    )
    (net (code "87") (name "unconnected-(U13A-GPIO29{slash}E1_DIDV{slash}RG1_RXCTL{slash}M1M_RXDV{slash}M1P_TXEN-Pad64)") (class "Default")
      (node (ref "U13") (pin "64") (pinfunction "GPIO29/E1_DIDV/RG1_RXCTL/M1M_RXDV/M1P_TXEN_64") (pintype "passive+no_connect"))
    )
    (net (code "88") (name "unconnected-(U13A-GPIO30{slash}E1_DI0{slash}RG1_RXD0{slash}M1M_RXD0{slash}M1P_TXD0-Pad65)") (class "Default")
      (node (ref "U13") (pin "65") (pinfunction "GPIO30/E1_DI0/RG1_RXD0/M1M_RXD0/M1P_TXD0_65") (pintype "passive+no_connect"))
    )
    (net (code "89") (name "unconnected-(U13A-GPIO57{slash}INTERRUPT-Pad19)") (class "Default")
      (node (ref "U13") (pin "19") (pinfunction "GPIO57/INTERRUPT_19") (pintype "passive+no_connect"))
    )
    (net (code "90") (name "unconnected-(U13A-GPO58{slash}DIS_LPD-Pad20)") (class "Default")
      (node (ref "U13") (pin "20") (pinfunction "GPO58/DIS_LPD_20") (pintype "passive+no_connect"))
    )
    (net (code "91") (name "unconnected-(U13A-NC2-Pad22)") (class "Default")
      (node (ref "U13") (pin "22") (pinfunction "NC2_22") (pintype "passive+no_connect"))
    )
    (net (code "92") (name "unconnected-(U13A-NC3-Pad35)") (class "Default")
      (node (ref "U13") (pin "35") (pinfunction "NC3_35") (pintype "passive+no_connect"))
    )
    (net (code "93") (name "unconnected-(U13A-NC4-Pad37)") (class "Default")
      (node (ref "U13") (pin "37") (pinfunction "NC4_37") (pintype "passive+no_connect"))
    )
    (net (code "94") (name "unconnected-(U13A-NC5-Pad38)") (class "Default")
      (node (ref "U13") (pin "38") (pinfunction "NC5_38") (pintype "passive+no_connect"))
    )
    (net (code "95") (name "unconnected-(U13A-P4MDIAN-Pad25)") (class "Default")
      (node (ref "U13") (pin "25") (pinfunction "P4MDIAN_25") (pintype "passive+no_connect"))
    )
    (net (code "96") (name "unconnected-(U13A-P4MDIAP-Pad24)") (class "Default")
      (node (ref "U13") (pin "24") (pinfunction "P4MDIAP_24") (pintype "passive+no_connect"))
    )
    (net (code "97") (name "unconnected-(U13A-P4MDIBN-Pad27)") (class "Default")
      (node (ref "U13") (pin "27") (pinfunction "P4MDIBN_27") (pintype "passive+no_connect"))
    )
    (net (code "98") (name "unconnected-(U13A-P4MDIBP-Pad26)") (class "Default")
      (node (ref "U13") (pin "26") (pinfunction "P4MDIBP_26") (pintype "passive+no_connect"))
    )
    (net (code "99") (name "unconnected-(U13A-P4MDICN-Pad30)") (class "Default")
      (node (ref "U13") (pin "30") (pinfunction "P4MDICN_30") (pintype "passive+no_connect"))
    )
    (net (code "100") (name "unconnected-(U13A-P4MDICP-Pad29)") (class "Default")
      (node (ref "U13") (pin "29") (pinfunction "P4MDICP_29") (pintype "passive+no_connect"))
    )
    (net (code "101") (name "unconnected-(U13A-P4MDIDN-Pad32)") (class "Default")
      (node (ref "U13") (pin "32") (pinfunction "P4MDIDN_32") (pintype "passive+no_connect"))
    )
    (net (code "102") (name "unconnected-(U13A-P4MDIDP-Pad31)") (class "Default")
      (node (ref "U13") (pin "31") (pinfunction "P4MDIDP_31") (pintype "passive+no_connect"))
    )
    (net (code "103") (name "unconnected-(U13A-RTT1-Pad15)") (class "Default")
      (node (ref "U13") (pin "15") (pinfunction "RTT1_15") (pintype "passive+no_connect"))
    )
    (net (code "104") (name "unconnected-(U13A-RTT2-Pad16)") (class "Default")
      (node (ref "U13") (pin "16") (pinfunction "RTT2_16") (pintype "passive+no_connect"))
    )
    (net (code "105") (name "unconnected-(U13B-ATESTCK0-Pad117)") (class "Default")
      (node (ref "U13") (pin "117") (pinfunction "ATESTCK0_117") (pintype "passive+no_connect"))
    )
    (net (code "106") (name "unconnected-(U13B-GPIO31{slash}E1_DI1{slash}RG1_RXD1{slash}M1M_RXD1{slash}M1P_TXD1-Pad66)") (class "Default")
      (node (ref "U13") (pin "66") (pinfunction "GPIO31/E1_DI1/RG1_RXD1/M1M_RXD1/M1P_TXD1_66") (pintype "passive+no_connect"))
    )
    (net (code "107") (name "unconnected-(U13B-GPIO32{slash}E1_DI2{slash}RG1_RXD2{slash}M1M_RXD2{slash}M1P_TXD2-Pad67)") (class "Default")
      (node (ref "U13") (pin "67") (pinfunction "GPIO32/E1_DI2/RG1_RXD2/M1M_RXD2/M1P_TXD2_67") (pintype "passive+no_connect"))
    )
    (net (code "108") (name "unconnected-(U13B-GPIO33{slash}E1_DI3{slash}RG1_RXD3{slash}M1M_RXD3{slash}M1P_TXD3-Pad68)") (class "Default")
      (node (ref "U13") (pin "68") (pinfunction "GPIO33/E1_DI3/RG1_RXD3/M1M_RXD3/M1P_TXD3_68") (pintype "passive+no_connect"))
    )
    (net (code "109") (name "unconnected-(U13B-NC-Pad87)") (class "Default")
      (node (ref "U13") (pin "87") (pinfunction "NC_87") (pintype "passive+no_connect"))
    )
  )
)
